# Sheet1.net
KiCad netlist of a schematic drawn in Altium Designer
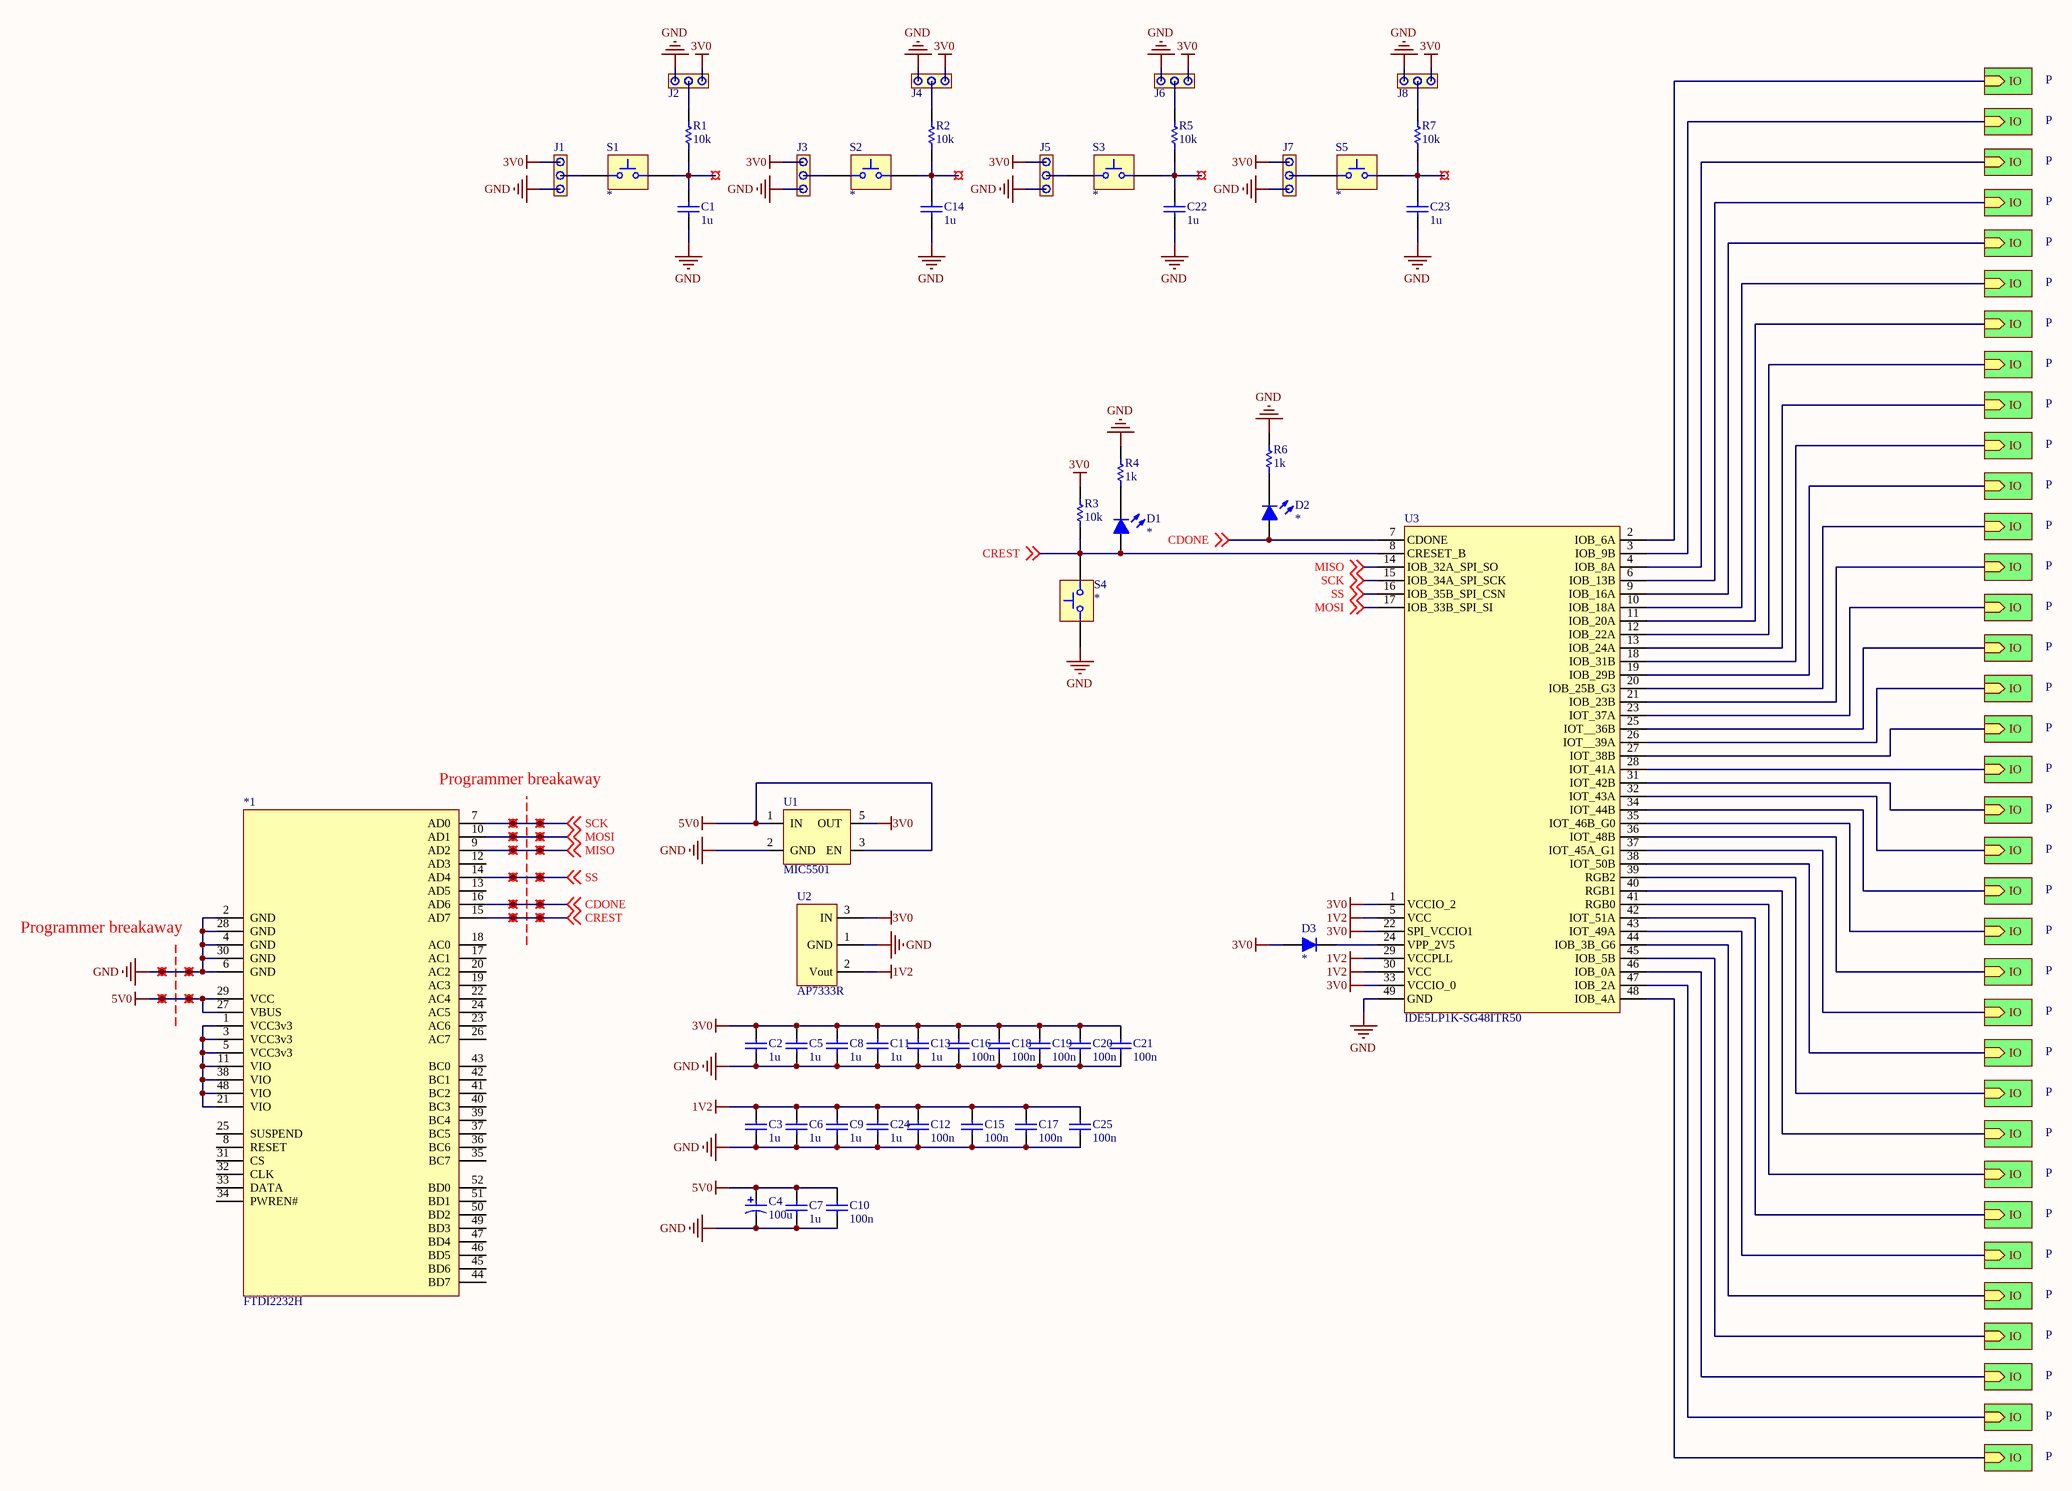
[diagram p0: Sheet1.SchDoc]

(export (version "E")
  (design (tool "Eeschema 10.0.6"))
  (components
    (comp (ref "*") (value "Logo") (footprint "ALogo") (libsource (lib "A_Speciality") (part "Logo")))
    (comp (ref "*1")
      (value "FTDI2232H")
      (footprint "FTDI2232H")
      (libsource (lib "A_Speciality") (part "FTDI2232H"))
    )
    (comp (ref "C1")
      (value "1u")
      (footprint "CAP 0805_N")
      (description "CAP, CER")
      (libsource (lib "Passive Components") (part "-Cap Non-Pol"))
    )
    (comp (ref "C2")
      (value "1u")
      (footprint "CAP 0805_N")
      (description "CAP, CER")
      (libsource (lib "Passive Components") (part "-Cap Non-Pol"))
    )
    (comp (ref "C3")
      (value "1u")
      (footprint "CAP 0805_N")
      (description "CAP, CER")
      (libsource (lib "Passive Components") (part "-Cap Non-Pol"))
    )
    (comp (ref "C4")
      (value "100u")
      (footprint "SMD CAP-6.3X7.7MM-A1K2")
      (description "CAP, ALUM, A1K2")
      (libsource (lib "Passive Components") (part "-Cap Aluminum"))
    )
    (comp (ref "C5")
      (value "1u")
      (footprint "CAP 0805_N")
      (description "CAP, CER")
      (libsource (lib "Passive Components") (part "-Cap Non-Pol"))
    )
    (comp (ref "C6")
      (value "1u")
      (footprint "CAP 0805_N")
      (description "CAP, CER")
      (libsource (lib "Passive Components") (part "-Cap Non-Pol"))
    )
    (comp (ref "C7")
      (value "1u")
      (footprint "CAP 0805_N")
      (description "CAP, CER")
      (libsource (lib "Passive Components") (part "-Cap Non-Pol"))
    )
    (comp (ref "C8")
      (value "1u")
      (footprint "CAP 0805_N")
      (description "CAP, CER")
      (libsource (lib "Passive Components") (part "-Cap Non-Pol"))
    )
    (comp (ref "C9")
      (value "1u")
      (footprint "CAP 0805_N")
      (description "CAP, CER")
      (libsource (lib "Passive Components") (part "-Cap Non-Pol"))
    )
    (comp (ref "C10")
      (value "100n")
      (footprint "CAP 0603_N")
      (description "CAP, CER")
      (libsource (lib "Passive Components") (part "-Cap Non-Pol"))
    )
    (comp (ref "C11")
      (value "1u")
      (footprint "CAP 0805_N")
      (description "CAP, CER")
      (libsource (lib "Passive Components") (part "-Cap Non-Pol"))
    )
    (comp (ref "C12")
      (value "100n")
      (footprint "CAP 0603_N")
      (description "CAP, CER")
      (libsource (lib "Passive Components") (part "-Cap Non-Pol"))
    )
    (comp (ref "C13")
      (value "1u")
      (footprint "CAP 0805_N")
      (description "CAP, CER")
      (libsource (lib "Passive Components") (part "-Cap Non-Pol"))
    )
    (comp (ref "C14")
      (value "1u")
      (footprint "CAP 0805_N")
      (description "CAP, CER")
      (libsource (lib "Passive Components") (part "-Cap Non-Pol"))
    )
    (comp (ref "C15")
      (value "100n")
      (footprint "CAP 0603_N")
      (description "CAP, CER")
      (libsource (lib "Passive Components") (part "-Cap Non-Pol"))
    )
    (comp (ref "C16")
      (value "100n")
      (footprint "CAP 0603_N")
      (description "CAP, CER")
      (libsource (lib "Passive Components") (part "-Cap Non-Pol"))
    )
    (comp (ref "C17")
      (value "100n")
      (footprint "CAP 0603_N")
      (description "CAP, CER")
      (libsource (lib "Passive Components") (part "-Cap Non-Pol"))
    )
    (comp (ref "C18")
      (value "100n")
      (footprint "CAP 0603_N")
      (description "CAP, CER")
      (libsource (lib "Passive Components") (part "-Cap Non-Pol"))
    )
    (comp (ref "C19")
      (value "100n")
      (footprint "CAP 0603_N")
      (description "CAP, CER")
      (libsource (lib "Passive Components") (part "-Cap Non-Pol"))
    )
    (comp (ref "C20")
      (value "100n")
      (footprint "CAP 0603_N")
      (description "CAP, CER")
      (libsource (lib "Passive Components") (part "-Cap Non-Pol"))
    )
    (comp (ref "C21")
      (value "100n")
      (footprint "CAP 0603_N")
      (description "CAP, CER")
      (libsource (lib "Passive Components") (part "-Cap Non-Pol"))
    )
    (comp (ref "C22")
      (value "1u")
      (footprint "CAP 0805_N")
      (description "CAP, CER")
      (libsource (lib "Passive Components") (part "-Cap Non-Pol"))
    )
    (comp (ref "C23")
      (value "1u")
      (footprint "CAP 0805_N")
      (description "CAP, CER")
      (libsource (lib "Passive Components") (part "-Cap Non-Pol"))
    )
    (comp (ref "C24")
      (value "1u")
      (footprint "CAP 0805_N")
      (description "CAP, CER")
      (libsource (lib "Passive Components") (part "-Cap Non-Pol"))
    )
    (comp (ref "C25")
      (value "100n")
      (footprint "CAP 0603_N")
      (description "CAP, CER")
      (libsource (lib "Passive Components") (part "-Cap Non-Pol"))
    )
    (comp (ref "D1")
      (value "~")
      (footprint "LED-0603-K1A2")
      (description "2 Pin LED K1A2")
      (fields (field (name "LABEL") "*"))
      (libsource (lib "Semiconductors") (part "-LED K1A2"))
    )
    (comp (ref "D2")
      (value "~")
      (footprint "LED-0603-K1A2")
      (description "2 Pin LED K1A2")
      (fields (field (name "LABEL") "*"))
      (libsource (lib "Semiconductors") (part "-LED K1A2"))
    )
    (comp (ref "D3")
      (value "*")
      (footprint "SMA_L-K1A2")
      (description "2 Pin Diode K1A2")
      (libsource (lib "Semiconductors") (part "-Diode K1A2"))
    )
    (comp (ref "J1")
      (value "~")
      (footprint "HDR1X3 VERT")
      (description "Header, 3 Pin, 1.27mm Pitch, Vertical")
      (libsource (lib "") (part "Header 1-3_1"))
    )
    (comp (ref "J2")
      (value "~")
      (footprint "HDR1X3 VERT")
      (description "Header, 3 Pin, 1.27mm Pitch, Vertical")
      (libsource (lib "A_Connector") (part "Header 1-3"))
    )
    (comp (ref "J3")
      (value "~")
      (footprint "HDR1X3 VERT")
      (description "Header, 3 Pin, 1.27mm Pitch, Vertical")
      (libsource (lib "") (part "Header 1-3_1"))
    )
    (comp (ref "J4")
      (value "~")
      (footprint "HDR1X3 VERT")
      (description "Header, 3 Pin, 1.27mm Pitch, Vertical")
      (libsource (lib "A_Connector") (part "Header 1-3"))
    )
    (comp (ref "J5")
      (value "~")
      (footprint "HDR1X3 VERT")
      (description "Header, 3 Pin, 1.27mm Pitch, Vertical")
      (libsource (lib "") (part "Header 1-3_1"))
    )
    (comp (ref "J6")
      (value "~")
      (footprint "HDR1X3 VERT")
      (description "Header, 3 Pin, 1.27mm Pitch, Vertical")
      (libsource (lib "A_Connector") (part "Header 1-3"))
    )
    (comp (ref "J7")
      (value "~")
      (footprint "HDR1X3 VERT")
      (description "Header, 3 Pin, 1.27mm Pitch, Vertical")
      (libsource (lib "") (part "Header 1-3_1"))
    )
    (comp (ref "J8")
      (value "~")
      (footprint "HDR1X3 VERT")
      (description "Header, 3 Pin, 1.27mm Pitch, Vertical")
      (libsource (lib "A_Connector") (part "Header 1-3"))
    )
    (comp (ref "R1")
      (value "10k")
      (footprint "RES 0603_N")
      (description "Resistor")
      (fields (field (name "Comment") "Res") (field (name "PUBLISHER") "Altium Limited"))
      (libsource (lib "Austin_Components") (part "Res"))
    )
    (comp (ref "R2")
      (value "10k")
      (footprint "RES 0603_N")
      (description "Resistor")
      (fields (field (name "Comment") "Res") (field (name "PUBLISHER") "Altium Limited"))
      (libsource (lib "Austin_Components") (part "Res"))
    )
    (comp (ref "R3")
      (value "10k")
      (footprint "RES 0603_N")
      (description "Resistor")
      (fields (field (name "Comment") "Res") (field (name "PUBLISHER") "Altium Limited"))
      (libsource (lib "Austin_Components") (part "Res"))
    )
    (comp (ref "R4")
      (value "1k")
      (footprint "RES 0603_N")
      (description "Resistor")
      (fields (field (name "Comment") "Res") (field (name "PUBLISHER") "Altium Limited"))
      (libsource (lib "Austin_Components") (part "Res"))
    )
    (comp (ref "R5")
      (value "10k")
      (footprint "RES 0603_N")
      (description "Resistor")
      (fields (field (name "Comment") "Res") (field (name "PUBLISHER") "Altium Limited"))
      (libsource (lib "Austin_Components") (part "Res"))
    )
    (comp (ref "R6")
      (value "1k")
      (footprint "RES 0603_N")
      (description "Resistor")
      (fields (field (name "Comment") "Res") (field (name "PUBLISHER") "Altium Limited"))
      (libsource (lib "Austin_Components") (part "Res"))
    )
    (comp (ref "R7")
      (value "10k")
      (footprint "RES 0603_N")
      (description "Resistor")
      (fields (field (name "Comment") "Res") (field (name "PUBLISHER") "Altium Limited"))
      (libsource (lib "Austin_Components") (part "Res"))
    )
    (comp (ref "S1")
      (value "SW Tactile")
      (footprint "SW-TACT-SMD-6035")
      (description "SPST, Normally Open, Push Button")
      (fields (field (name "LABEL") "*"))
      (libsource (lib "") (part "SW-NO (PTS635SH43SMTRLFS)_1"))
    )
    (comp (ref "S2")
      (value "SW Tactile")
      (footprint "SW-TACT-SMD-6035")
      (description "SPST, Normally Open, Push Button")
      (fields (field (name "LABEL") "*"))
      (libsource (lib "") (part "SW-NO (PTS635SH43SMTRLFS)_1"))
    )
    (comp (ref "S3")
      (value "SW Tactile")
      (footprint "SW-TACT-SMD-6035")
      (description "SPST, Normally Open, Push Button")
      (fields (field (name "LABEL") "*"))
      (libsource (lib "") (part "SW-NO (PTS635SH43SMTRLFS)_1"))
    )
    (comp (ref "S4")
      (value "SW Tactile")
      (footprint "SW-TACT-SMD-6035")
      (description "SPST, Normally Open, Push Button")
      (fields (field (name "LABEL") "*"))
      (libsource (lib "Electromechanical") (part "SW-NO (PTS635SH43SMTRLFS)"))
    )
    (comp (ref "S5")
      (value "SW Tactile")
      (footprint "SW-TACT-SMD-6035")
      (description "SPST, Normally Open, Push Button")
      (fields (field (name "LABEL") "*"))
      (libsource (lib "") (part "SW-NO (PTS635SH43SMTRLFS)_1"))
    )
    (comp (ref "TP1") (value "~") (footprint "THTP") (libsource (lib "A_Speciality") (part "THTP")))
    (comp (ref "TP2") (value "~") (footprint "THTP") (libsource (lib "A_Speciality") (part "THTP")))
    (comp (ref "TP3") (value "~") (footprint "THTP") (libsource (lib "A_Speciality") (part "THTP")))
    (comp (ref "TP4") (value "~") (footprint "THTP") (libsource (lib "A_Speciality") (part "THTP")))
    (comp (ref "TP5") (value "~") (footprint "THTP") (libsource (lib "A_Speciality") (part "THTP")))
    (comp (ref "TP6") (value "~") (footprint "THTP") (libsource (lib "A_Speciality") (part "THTP")))
    (comp (ref "TP7") (value "~") (footprint "THTP") (libsource (lib "A_Speciality") (part "THTP")))
    (comp (ref "TP8") (value "~") (footprint "THTP") (libsource (lib "A_Speciality") (part "THTP")))
    (comp (ref "TP9") (value "~") (footprint "THTP") (libsource (lib "A_Speciality") (part "THTP")))
    (comp (ref "TP10") (value "~") (footprint "THTP") (libsource (lib "A_Speciality") (part "THTP")))
    (comp (ref "TP11") (value "~") (footprint "THTP") (libsource (lib "A_Speciality") (part "THTP")))
    (comp (ref "TP12") (value "~") (footprint "THTP") (libsource (lib "A_Speciality") (part "THTP")))
    (comp (ref "TP13") (value "~") (footprint "THTP") (libsource (lib "A_Speciality") (part "THTP")))
    (comp (ref "TP14") (value "~") (footprint "THTP") (libsource (lib "A_Speciality") (part "THTP")))
    (comp (ref "TP15") (value "~") (footprint "THTP") (libsource (lib "A_Speciality") (part "THTP")))
    (comp (ref "TP16") (value "~") (footprint "THTP") (libsource (lib "A_Speciality") (part "THTP")))
    (comp (ref "TP17") (value "~") (footprint "THTP") (libsource (lib "A_Speciality") (part "THTP")))
    (comp (ref "TP26") (value "~") (footprint "THTP") (libsource (lib "A_Speciality") (part "THTP")))
    (comp (ref "TP28") (value "~") (footprint "THTP") (libsource (lib "A_Speciality") (part "THTP")))
    (comp (ref "TP30") (value "~") (footprint "THTP") (libsource (lib "A_Speciality") (part "THTP")))
    (comp (ref "U1") (value "MIC5501") (footprint "SOT23-5") (libsource (lib "A_Semi") (part "LP5907")))
    (comp (ref "U2")
      (value "AP7333R")
      (footprint "SOT95P245X110-3N")
      (libsource (lib "A_Semi") (part "AP7333R"))
    )
    (comp (ref "U3")
      (value "IDE5LP1K-SG48ITR50")
      (footprint "QFN50P700X700X85_HS-49M")
      (libsource (lib "A_Semi") (part "IDE5LP1K-SG48ITR50"))
    )
  )
  (nets
    (net (code "1") (name "/IO") (class "Default")
      (node (ref "U3") (pin "48") (pinfunction "IOB_4A_48") (pintype "passive"))
    )
    (net (code "2") (name "/IO_1") (class "Default")
      (node (ref "U3") (pin "45") (pinfunction "IOB_5B_45") (pintype "passive"))
    )
    (net (code "3") (name "/IO_2") (class "Default")
      (node (ref "U3") (pin "44") (pinfunction "IOB_3B_G6_44") (pintype "passive"))
    )
    (net (code "4") (name "/IO_3") (class "Default")
      (node (ref "U3") (pin "43") (pinfunction "IOT_49A_43") (pintype "passive"))
    )
    (net (code "5") (name "/IO_4") (class "Default")
      (node (ref "U3") (pin "42") (pinfunction "IOT_51A_42") (pintype "passive"))
    )
    (net (code "6") (name "/IO_5") (class "Default")
      (node (ref "U3") (pin "41") (pinfunction "RGB0_41") (pintype "passive"))
    )
    (net (code "7") (name "/IO_6") (class "Default")
      (node (ref "U3") (pin "40") (pinfunction "RGB1_40") (pintype "passive"))
    )
    (net (code "8") (name "/IO_7") (class "Default")
      (node (ref "U3") (pin "2") (pinfunction "IOB_6A_2") (pintype "passive"))
    )
    (net (code "9") (name "/IO_8") (class "Default")
      (node (ref "U3") (pin "3") (pinfunction "IOB_9B_3") (pintype "passive"))
    )
    (net (code "10") (name "/IO_9") (class "Default")
      (node (ref "U3") (pin "4") (pinfunction "IOB_8A_4") (pintype "passive"))
    )
    (net (code "11") (name "/IO_10") (class "Default")
      (node (ref "U3") (pin "6") (pinfunction "IOB_13B_6") (pintype "passive"))
    )
    (net (code "12") (name "/IO_11") (class "Default")
      (node (ref "U3") (pin "9") (pinfunction "IOB_16A_9") (pintype "passive"))
    )
    (net (code "13") (name "/IO_12") (class "Default")
      (node (ref "U3") (pin "10") (pinfunction "IOB_18A_10") (pintype "passive"))
    )
    (net (code "14") (name "/IO_13") (class "Default")
      (node (ref "U3") (pin "11") (pinfunction "IOB_20A_11") (pintype "passive"))
    )
    (net (code "15") (name "/IO_14") (class "Default")
      (node (ref "U3") (pin "12") (pinfunction "IOB_22A_12") (pintype "passive"))
    )
    (net (code "16") (name "/IO_15") (class "Default")
      (node (ref "U3") (pin "13") (pinfunction "IOB_24A_13") (pintype "passive"))
    )
    (net (code "17") (name "/IO_16") (class "Default")
      (node (ref "U3") (pin "18") (pinfunction "IOB_31B_18") (pintype "passive"))
    )
    (net (code "18") (name "/IO_17") (class "Default")
      (node (ref "U3") (pin "19") (pinfunction "IOB_29B_19") (pintype "passive"))
    )
    (net (code "19") (name "/IO_18") (class "Default")
      (node (ref "U3") (pin "20") (pinfunction "IOB_25B_G3_20") (pintype "passive"))
    )
    (net (code "20") (name "/IO_19") (class "Default")
      (node (ref "U3") (pin "21") (pinfunction "IOB_23B_21") (pintype "passive"))
    )
    (net (code "21") (name "/IO_20") (class "Default")
      (node (ref "U3") (pin "23") (pinfunction "IOT_37A_23") (pintype "passive"))
    )
    (net (code "22") (name "/IO_21") (class "Default")
      (node (ref "U3") (pin "25") (pinfunction "IOT__36B_25") (pintype "passive"))
    )
    (net (code "23") (name "/IO_22") (class "Default")
      (node (ref "U3") (pin "26") (pinfunction "IOT__39A_26") (pintype "passive"))
    )
    (net (code "24") (name "/IO_23") (class "Default")
      (node (ref "U3") (pin "27") (pinfunction "IOT_38B_27") (pintype "passive"))
    )
    (net (code "25") (name "/IO_24") (class "Default")
      (node (ref "U3") (pin "28") (pinfunction "IOT_41A_28") (pintype "passive"))
    )
    (net (code "26") (name "/IO_25") (class "Default")
      (node (ref "U3") (pin "31") (pinfunction "IOT_42B_31") (pintype "passive"))
    )
    (net (code "27") (name "/IO_26") (class "Default")
      (node (ref "U3") (pin "32") (pinfunction "IOT_43A_32") (pintype "passive"))
    )
    (net (code "28") (name "/IO_27") (class "Default")
      (node (ref "U3") (pin "34") (pinfunction "IOT_44B_34") (pintype "passive"))
    )
    (net (code "29") (name "/IO_28") (class "Default")
      (node (ref "U3") (pin "35") (pinfunction "IOT_46B_G0_35") (pintype "passive"))
    )
    (net (code "30") (name "/IO_29") (class "Default")
      (node (ref "U3") (pin "36") (pinfunction "IOT_48B_36") (pintype "passive"))
    )
    (net (code "31") (name "/IO_30") (class "Default")
      (node (ref "U3") (pin "37") (pinfunction "IOT_45A_G1_37") (pintype "passive"))
    )
    (net (code "32") (name "/IO_31") (class "Default")
      (node (ref "U3") (pin "38") (pinfunction "IOT_50B_38") (pintype "passive"))
    )
    (net (code "33") (name "/IO_32") (class "Default")
      (node (ref "U3") (pin "39") (pinfunction "RGB2_39") (pintype "passive"))
    )
    (net (code "34") (name "/IO_33") (class "Default")
      (node (ref "U3") (pin "46") (pinfunction "IOB_0A_46") (pintype "passive"))
    )
    (net (code "35") (name "/IO_34") (class "Default")
      (node (ref "U3") (pin "47") (pinfunction "IOB_2A_47") (pintype "passive"))
    )
    (net (code "36") (name "1V2") (class "Default")
      (node (ref "C12") (pin "1") (pinfunction "1_1") (pintype "passive"))
      (node (ref "C15") (pin "1") (pinfunction "1_1") (pintype "passive"))
      (node (ref "C17") (pin "1") (pinfunction "1_1") (pintype "passive"))
      (node (ref "C24") (pin "1") (pinfunction "1_1") (pintype "passive"))
      (node (ref "C25") (pin "1") (pinfunction "1_1") (pintype "passive"))
      (node (ref "C3") (pin "1") (pinfunction "1_1") (pintype "passive"))
      (node (ref "C6") (pin "1") (pinfunction "1_1") (pintype "passive"))
      (node (ref "C9") (pin "1") (pinfunction "1_1") (pintype "passive"))
      (node (ref "U2") (pin "2") (pinfunction "Vout_2") (pintype "passive"))
      (node (ref "U3") (pin "29") (pinfunction "VCCPLL_29") (pintype "passive"))
      (node (ref "U3") (pin "30") (pinfunction "VCC_30") (pintype "passive"))
      (node (ref "U3") (pin "5") (pinfunction "VCC_5") (pintype "passive"))
    )
    (net (code "37") (name "3V0") (class "Default")
      (node (ref "C11") (pin "1") (pinfunction "1_1") (pintype "passive"))
      (node (ref "C13") (pin "1") (pinfunction "1_1") (pintype "passive"))
      (node (ref "C16") (pin "1") (pinfunction "1_1") (pintype "passive"))
      (node (ref "C18") (pin "1") (pinfunction "1_1") (pintype "passive"))
      (node (ref "C19") (pin "1") (pinfunction "1_1") (pintype "passive"))
      (node (ref "C2") (pin "1") (pinfunction "1_1") (pintype "passive"))
      (node (ref "C20") (pin "1") (pinfunction "1_1") (pintype "passive"))
      (node (ref "C21") (pin "1") (pinfunction "1_1") (pintype "passive"))
      (node (ref "C5") (pin "1") (pinfunction "1_1") (pintype "passive"))
      (node (ref "C8") (pin "1") (pinfunction "1_1") (pintype "passive"))
      (node (ref "D3") (pin "2") (pinfunction "A_2") (pintype "passive"))
      (node (ref "J1") (pin "3") (pinfunction "3_3") (pintype "passive"))
      (node (ref "J2") (pin "1") (pinfunction "1_1") (pintype "passive"))
      (node (ref "J3") (pin "3") (pinfunction "3_3") (pintype "passive"))
      (node (ref "J4") (pin "1") (pinfunction "1_1") (pintype "passive"))
      (node (ref "J5") (pin "3") (pinfunction "3_3") (pintype "passive"))
      (node (ref "J6") (pin "1") (pinfunction "1_1") (pintype "passive"))
      (node (ref "J7") (pin "3") (pinfunction "3_3") (pintype "passive"))
      (node (ref "J8") (pin "1") (pinfunction "1_1") (pintype "passive"))
      (node (ref "R3") (pin "2") (pinfunction "2_2") (pintype "passive"))
      (node (ref "U1") (pin "5") (pinfunction "OUT_5") (pintype "passive"))
      (node (ref "U2") (pin "3") (pinfunction "IN_3") (pintype "passive"))
      (node (ref "U3") (pin "1") (pinfunction "VCCIO_2_1") (pintype "passive"))
      (node (ref "U3") (pin "22") (pinfunction "SPI_VCCIO1_22") (pintype "passive"))
      (node (ref "U3") (pin "33") (pinfunction "VCCIO_0_33") (pintype "passive"))
    )
    (net (code "38") (name "5V0") (class "Default")
      (node (ref "*1") (pin "27") (pinfunction "VBUS_27") (pintype "passive"))
      (node (ref "*1") (pin "29") (pinfunction "VCC_29") (pintype "passive"))
      (node (ref "C10") (pin "1") (pinfunction "1_1") (pintype "passive"))
      (node (ref "C4") (pin "1") (pinfunction "A_1") (pintype "passive"))
      (node (ref "C7") (pin "1") (pinfunction "1_1") (pintype "passive"))
      (node (ref "TP2") (pin "1") (pintype "passive"))
      (node (ref "TP4") (pin "1") (pintype "passive"))
      (node (ref "U1") (pin "1") (pinfunction "IN_1") (pintype "passive"))
      (node (ref "U1") (pin "3") (pinfunction "EN_3") (pintype "passive"))
    )
    (net (code "39") (name "CDONE") (class "Default")
      (node (ref "*1") (pin "16") (pinfunction "AD6_16") (pintype "passive"))
      (node (ref "D2") (pin "2") (pinfunction "A_2") (pintype "passive"))
      (node (ref "TP15") (pin "1") (pintype "passive"))
      (node (ref "TP9") (pin "1") (pintype "passive"))
      (node (ref "U3") (pin "7") (pinfunction "CDONE_7") (pintype "passive"))
    )
    (net (code "40") (name "CREST") (class "Default")
      (node (ref "*1") (pin "15") (pinfunction "AD7_15") (pintype "passive"))
      (node (ref "D1") (pin "2") (pinfunction "A_2") (pintype "passive"))
      (node (ref "R3") (pin "1") (pinfunction "1_1") (pintype "passive"))
      (node (ref "S4") (pin "2") (pinfunction "2_2") (pintype "passive"))
      (node (ref "TP10") (pin "1") (pintype "passive"))
      (node (ref "TP16") (pin "1") (pintype "passive"))
      (node (ref "U3") (pin "8") (pinfunction "CRESET_B_8") (pintype "passive"))
    )
    (net (code "41") (name "GND") (class "Default")
      (node (ref "*1") (pin "2") (pinfunction "GND_2") (pintype "passive"))
      (node (ref "*1") (pin "28") (pinfunction "GND_28") (pintype "passive"))
      (node (ref "*1") (pin "30") (pinfunction "GND_30") (pintype "passive"))
      (node (ref "*1") (pin "4") (pinfunction "GND_4") (pintype "passive"))
      (node (ref "*1") (pin "6") (pinfunction "GND_6") (pintype "passive"))
      (node (ref "C1") (pin "2") (pinfunction "2_2") (pintype "passive"))
      (node (ref "C10") (pin "2") (pinfunction "2_2") (pintype "passive"))
      (node (ref "C11") (pin "2") (pinfunction "2_2") (pintype "passive"))
      (node (ref "C12") (pin "2") (pinfunction "2_2") (pintype "passive"))
      (node (ref "C13") (pin "2") (pinfunction "2_2") (pintype "passive"))
      (node (ref "C14") (pin "2") (pinfunction "2_2") (pintype "passive"))
      (node (ref "C15") (pin "2") (pinfunction "2_2") (pintype "passive"))
      (node (ref "C16") (pin "2") (pinfunction "2_2") (pintype "passive"))
      (node (ref "C17") (pin "2") (pinfunction "2_2") (pintype "passive"))
      (node (ref "C18") (pin "2") (pinfunction "2_2") (pintype "passive"))
      (node (ref "C19") (pin "2") (pinfunction "2_2") (pintype "passive"))
      (node (ref "C2") (pin "2") (pinfunction "2_2") (pintype "passive"))
      (node (ref "C20") (pin "2") (pinfunction "2_2") (pintype "passive"))
      (node (ref "C21") (pin "2") (pinfunction "2_2") (pintype "passive"))
      (node (ref "C22") (pin "2") (pinfunction "2_2") (pintype "passive"))
      (node (ref "C23") (pin "2") (pinfunction "2_2") (pintype "passive"))
      (node (ref "C24") (pin "2") (pinfunction "2_2") (pintype "passive"))
      (node (ref "C25") (pin "2") (pinfunction "2_2") (pintype "passive"))
      (node (ref "C3") (pin "2") (pinfunction "2_2") (pintype "passive"))
      (node (ref "C4") (pin "2") (pinfunction "K_2") (pintype "passive"))
      (node (ref "C5") (pin "2") (pinfunction "2_2") (pintype "passive"))
      (node (ref "C6") (pin "2") (pinfunction "2_2") (pintype "passive"))
      (node (ref "C7") (pin "2") (pinfunction "2_2") (pintype "passive"))
      (node (ref "C8") (pin "2") (pinfunction "2_2") (pintype "passive"))
      (node (ref "C9") (pin "2") (pinfunction "2_2") (pintype "passive"))
      (node (ref "J1") (pin "1") (pinfunction "1_1") (pintype "passive"))
      (node (ref "J2") (pin "3") (pinfunction "3_3") (pintype "passive"))
      (node (ref "J3") (pin "1") (pinfunction "1_1") (pintype "passive"))
      (node (ref "J4") (pin "3") (pinfunction "3_3") (pintype "passive"))
      (node (ref "J5") (pin "1") (pinfunction "1_1") (pintype "passive"))
      (node (ref "J6") (pin "3") (pinfunction "3_3") (pintype "passive"))
      (node (ref "J7") (pin "1") (pinfunction "1_1") (pintype "passive"))
      (node (ref "J8") (pin "3") (pinfunction "3_3") (pintype "passive"))
      (node (ref "R4") (pin "1") (pinfunction "1_1") (pintype "passive"))
      (node (ref "R6") (pin "1") (pinfunction "1_1") (pintype "passive"))
      (node (ref "S4") (pin "1") (pinfunction "1_1") (pintype "passive"))
      (node (ref "TP1") (pin "1") (pintype "passive"))
      (node (ref "TP3") (pin "1") (pintype "passive"))
      (node (ref "U1") (pin "2") (pinfunction "GND_2") (pintype "passive"))
      (node (ref "U2") (pin "1") (pinfunction "GND_1") (pintype "passive"))
      (node (ref "U3") (pin "49") (pinfunction "GND_49") (pintype "passive"))
    )
    (net (code "42") (name "MISO") (class "Default")
      (node (ref "*1") (pin "9") (pinfunction "AD2_9") (pintype "passive"))
      (node (ref "TP13") (pin "1") (pintype "passive"))
      (node (ref "TP7") (pin "1") (pintype "passive"))
      (node (ref "U3") (pin "14") (pinfunction "IOB_32A_SPI_SO_14") (pintype "passive"))
    )
    (net (code "43") (name "MOSI") (class "Default")
      (node (ref "*1") (pin "10") (pinfunction "AD1_10") (pintype "passive"))
      (node (ref "TP12") (pin "1") (pintype "passive"))
      (node (ref "TP6") (pin "1") (pintype "passive"))
      (node (ref "U3") (pin "17") (pinfunction "IOB_33B_SPI_SI_17") (pintype "passive"))
    )
    (net (code "44") (name "Net-(*1-VCC3v3-Pad1)") (class "Default")
      (node (ref "*1") (pin "1") (pinfunction "VCC3v3_1") (pintype "passive"))
      (node (ref "*1") (pin "11") (pinfunction "VIO_11") (pintype "passive"))
      (node (ref "*1") (pin "21") (pinfunction "VIO_21") (pintype "passive"))
      (node (ref "*1") (pin "3") (pinfunction "VCC3v3_3") (pintype "passive"))
      (node (ref "*1") (pin "38") (pinfunction "VIO_38") (pintype "passive"))
      (node (ref "*1") (pin "48") (pinfunction "VIO_48") (pintype "passive"))
      (node (ref "*1") (pin "5") (pinfunction "VCC3v3_5") (pintype "passive"))
    )
    (net (code "45") (name "Net-(C1-Pad1)") (class "Default")
      (node (ref "C1") (pin "1") (pinfunction "1_1") (pintype "passive"))
      (node (ref "R1") (pin "1") (pinfunction "1_1") (pintype "passive"))
      (node (ref "S1") (pin "2") (pinfunction "2_2") (pintype "passive"))
      (node (ref "TP17") (pin "1") (pintype "passive"))
    )
    (net (code "46") (name "Net-(C14-Pad1)") (class "Default")
      (node (ref "C14") (pin "1") (pinfunction "1_1") (pintype "passive"))
      (node (ref "R2") (pin "1") (pinfunction "1_1") (pintype "passive"))
      (node (ref "S2") (pin "2") (pinfunction "2_2") (pintype "passive"))
      (node (ref "TP26") (pin "1") (pintype "passive"))
    )
    (net (code "47") (name "Net-(C22-Pad1)") (class "Default")
      (node (ref "C22") (pin "1") (pinfunction "1_1") (pintype "passive"))
      (node (ref "R5") (pin "1") (pinfunction "1_1") (pintype "passive"))
      (node (ref "S3") (pin "2") (pinfunction "2_2") (pintype "passive"))
      (node (ref "TP28") (pin "1") (pintype "passive"))
    )
    (net (code "48") (name "Net-(C23-Pad1)") (class "Default")
      (node (ref "C23") (pin "1") (pinfunction "1_1") (pintype "passive"))
      (node (ref "R7") (pin "1") (pinfunction "1_1") (pintype "passive"))
      (node (ref "S5") (pin "2") (pinfunction "2_2") (pintype "passive"))
      (node (ref "TP30") (pin "1") (pintype "passive"))
    )
    (net (code "49") (name "Net-(D1-K)") (class "Default")
      (node (ref "D1") (pin "1") (pinfunction "K_1") (pintype "passive"))
      (node (ref "R4") (pin "2") (pinfunction "2_2") (pintype "passive"))
    )
    (net (code "50") (name "Net-(D2-K)") (class "Default")
      (node (ref "D2") (pin "1") (pinfunction "K_1") (pintype "passive"))
      (node (ref "R6") (pin "2") (pinfunction "2_2") (pintype "passive"))
    )
    (net (code "51") (name "Net-(D3-K)") (class "Default")
      (node (ref "D3") (pin "1") (pinfunction "K_1") (pintype "passive"))
      (node (ref "U3") (pin "24") (pinfunction "VPP_2V5_24") (pintype "passive"))
    )
    (net (code "52") (name "Net-(J1-Pad2)") (class "Default")
      (node (ref "J1") (pin "2") (pinfunction "2_2") (pintype "passive"))
      (node (ref "S1") (pin "1") (pinfunction "1_1") (pintype "passive"))
    )
    (net (code "53") (name "Net-(J2-Pad2)") (class "Default")
      (node (ref "J2") (pin "2") (pinfunction "2_2") (pintype "passive"))
      (node (ref "R1") (pin "2") (pinfunction "2_2") (pintype "passive"))
    )
    (net (code "54") (name "Net-(J3-Pad2)") (class "Default")
      (node (ref "J3") (pin "2") (pinfunction "2_2") (pintype "passive"))
      (node (ref "S2") (pin "1") (pinfunction "1_1") (pintype "passive"))
    )
    (net (code "55") (name "Net-(J4-Pad2)") (class "Default")
      (node (ref "J4") (pin "2") (pinfunction "2_2") (pintype "passive"))
      (node (ref "R2") (pin "2") (pinfunction "2_2") (pintype "passive"))
    )
    (net (code "56") (name "Net-(J5-Pad2)") (class "Default")
      (node (ref "J5") (pin "2") (pinfunction "2_2") (pintype "passive"))
      (node (ref "S3") (pin "1") (pinfunction "1_1") (pintype "passive"))
    )
    (net (code "57") (name "Net-(J6-Pad2)") (class "Default")
      (node (ref "J6") (pin "2") (pinfunction "2_2") (pintype "passive"))
      (node (ref "R5") (pin "2") (pinfunction "2_2") (pintype "passive"))
    )
    (net (code "58") (name "Net-(J7-Pad2)") (class "Default")
      (node (ref "J7") (pin "2") (pinfunction "2_2") (pintype "passive"))
      (node (ref "S5") (pin "1") (pinfunction "1_1") (pintype "passive"))
    )
    (net (code "59") (name "Net-(J8-Pad2)") (class "Default")
      (node (ref "J8") (pin "2") (pinfunction "2_2") (pintype "passive"))
      (node (ref "R7") (pin "2") (pinfunction "2_2") (pintype "passive"))
    )
    (net (code "60") (name "SCK") (class "Default")
      (node (ref "*1") (pin "7") (pinfunction "AD0_7") (pintype "passive"))
      (node (ref "TP11") (pin "1") (pintype "passive"))
      (node (ref "TP5") (pin "1") (pintype "passive"))
      (node (ref "U3") (pin "15") (pinfunction "IOB_34A_SPI_SCK_15") (pintype "passive"))
    )
    (net (code "61") (name "SS") (class "Default")
      (node (ref "*1") (pin "14") (pinfunction "AD4_14") (pintype "passive"))
      (node (ref "TP14") (pin "1") (pintype "passive"))
      (node (ref "TP8") (pin "1") (pintype "passive"))
      (node (ref "U3") (pin "16") (pinfunction "IOB_35B_SPI_CSN_16") (pintype "passive"))
    )
    (net (code "62") (name "unconnected-(*1-AC0-Pad18)") (class "Default")
      (node (ref "*1") (pin "18") (pinfunction "AC0_18") (pintype "passive"))
    )
    (net (code "63") (name "unconnected-(*1-AC1-Pad17)") (class "Default")
      (node (ref "*1") (pin "17") (pinfunction "AC1_17") (pintype "passive"))
    )
    (net (code "64") (name "unconnected-(*1-AC2-Pad20)") (class "Default")
      (node (ref "*1") (pin "20") (pinfunction "AC2_20") (pintype "passive"))
    )
    (net (code "65") (name "unconnected-(*1-AC3-Pad19)") (class "Default")
      (node (ref "*1") (pin "19") (pinfunction "AC3_19") (pintype "passive"))
    )
    (net (code "66") (name "unconnected-(*1-AC4-Pad22)") (class "Default")
      (node (ref "*1") (pin "22") (pinfunction "AC4_22") (pintype "passive"))
    )
    (net (code "67") (name "unconnected-(*1-AC5-Pad24)") (class "Default")
      (node (ref "*1") (pin "24") (pinfunction "AC5_24") (pintype "passive"))
    )
    (net (code "68") (name "unconnected-(*1-AC6-Pad23)") (class "Default")
      (node (ref "*1") (pin "23") (pinfunction "AC6_23") (pintype "passive"))
    )
    (net (code "69") (name "unconnected-(*1-AC7-Pad26)") (class "Default")
      (node (ref "*1") (pin "26") (pinfunction "AC7_26") (pintype "passive"))
    )
    (net (code "70") (name "unconnected-(*1-AD3-Pad12)") (class "Default")
      (node (ref "*1") (pin "12") (pinfunction "AD3_12") (pintype "passive"))
    )
    (net (code "71") (name "unconnected-(*1-AD5-Pad13)") (class "Default")
      (node (ref "*1") (pin "13") (pinfunction "AD5_13") (pintype "passive"))
    )
    (net (code "72") (name "unconnected-(*1-BC0-Pad43)") (class "Default")
      (node (ref "*1") (pin "43") (pinfunction "BC0_43") (pintype "passive"))
    )
    (net (code "73") (name "unconnected-(*1-BC1-Pad42)") (class "Default")
      (node (ref "*1") (pin "42") (pinfunction "BC1_42") (pintype "passive"))
    )
    (net (code "74") (name "unconnected-(*1-BC2-Pad41)") (class "Default")
      (node (ref "*1") (pin "41") (pinfunction "BC2_41") (pintype "passive"))
    )
    (net (code "75") (name "unconnected-(*1-BC3-Pad40)") (class "Default")
      (node (ref "*1") (pin "40") (pinfunction "BC3_40") (pintype "passive"))
    )
    (net (code "76") (name "unconnected-(*1-BC4-Pad39)") (class "Default")
      (node (ref "*1") (pin "39") (pinfunction "BC4_39") (pintype "passive"))
    )
    (net (code "77") (name "unconnected-(*1-BC5-Pad37)") (class "Default")
      (node (ref "*1") (pin "37") (pinfunction "BC5_37") (pintype "passive"))
    )
    (net (code "78") (name "unconnected-(*1-BC6-Pad36)") (class "Default")
      (node (ref "*1") (pin "36") (pinfunction "BC6_36") (pintype "passive"))
    )
    (net (code "79") (name "unconnected-(*1-BC7-Pad35)") (class "Default")
      (node (ref "*1") (pin "35") (pinfunction "BC7_35") (pintype "passive"))
    )
    (net (code "80") (name "unconnected-(*1-BD0-Pad52)") (class "Default")
      (node (ref "*1") (pin "52") (pinfunction "BD0_52") (pintype "passive"))
    )
    (net (code "81") (name "unconnected-(*1-BD1-Pad51)") (class "Default")
      (node (ref "*1") (pin "51") (pinfunction "BD1_51") (pintype "passive"))
    )
    (net (code "82") (name "unconnected-(*1-BD2-Pad50)") (class "Default")
      (node (ref "*1") (pin "50") (pinfunction "BD2_50") (pintype "passive"))
    )
    (net (code "83") (name "unconnected-(*1-BD3-Pad49)") (class "Default")
      (node (ref "*1") (pin "49") (pinfunction "BD3_49") (pintype "passive"))
    )
    (net (code "84") (name "unconnected-(*1-BD4-Pad47)") (class "Default")
      (node (ref "*1") (pin "47") (pinfunction "BD4_47") (pintype "passive"))
    )
    (net (code "85") (name "unconnected-(*1-BD5-Pad46)") (class "Default")
      (node (ref "*1") (pin "46") (pinfunction "BD5_46") (pintype "passive"))
    )
    (net (code "86") (name "unconnected-(*1-BD6-Pad45)") (class "Default")
      (node (ref "*1") (pin "45") (pinfunction "BD6_45") (pintype "passive"))
    )
    (net (code "87") (name "unconnected-(*1-BD7-Pad44)") (class "Default")
      (node (ref "*1") (pin "44") (pinfunction "BD7_44") (pintype "passive"))
    )
    (net (code "88") (name "unconnected-(*1-CLK-Pad32)") (class "Default")
      (node (ref "*1") (pin "32") (pinfunction "CLK_32") (pintype "passive"))
    )
    (net (code "89") (name "unconnected-(*1-CS-Pad31)") (class "Default")
      (node (ref "*1") (pin "31") (pinfunction "CS_31") (pintype "passive"))
    )
    (net (code "90") (name "unconnected-(*1-DATA-Pad33)") (class "Default")
      (node (ref "*1") (pin "33") (pinfunction "DATA_33") (pintype "passive"))
    )
    (net (code "91") (name "unconnected-(*1-PWREN#-Pad34)") (class "Default")
      (node (ref "*1") (pin "34") (pinfunction "PWREN#_34") (pintype "passive"))
    )
    (net (code "92") (name "unconnected-(*1-RESET-Pad8)") (class "Default")
      (node (ref "*1") (pin "8") (pinfunction "RESET_8") (pintype "passive"))
    )
    (net (code "93") (name "unconnected-(*1-SUSPEND-Pad25)") (class "Default")
      (node (ref "*1") (pin "25") (pinfunction "SUSPEND_25") (pintype "passive"))
    )
  )
)
